# Atmega1280_xmem_512K.net
KiCad netlist of a schematic drawn in EAGLE
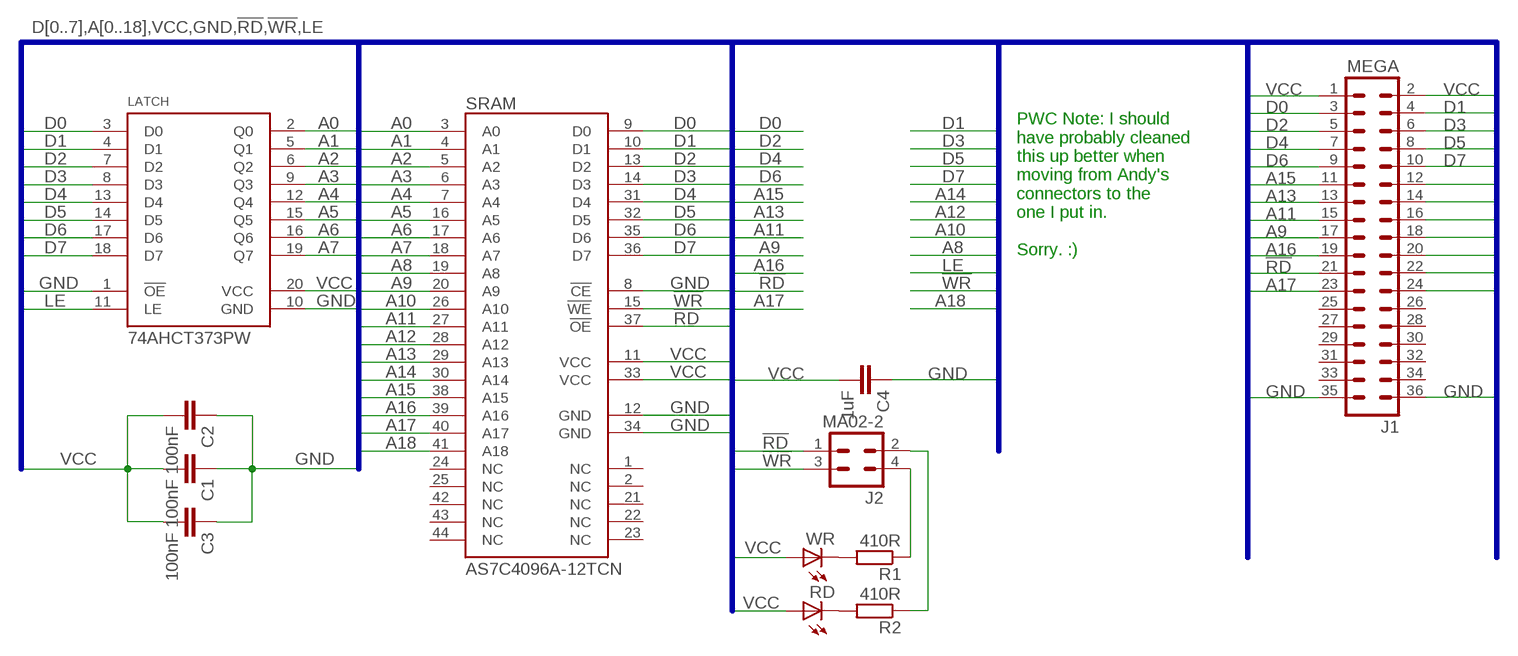
[diagram p0: schematic, sheet 1]

(export (version "E")
  (design (tool "Eeschema 10.0.6"))
  (components
    (comp (ref "C1")
      (value "100nF")
      (footprint "eagle-import:C0603")
      (libsource (lib "eagle-import") (part "C-EUC0603"))
    )
    (comp (ref "C2")
      (value "100nF")
      (footprint "eagle-import:C0603")
      (libsource (lib "eagle-import") (part "C-EUC0603"))
    )
    (comp (ref "C3")
      (value "100nF")
      (footprint "eagle-import:C0603")
      (libsource (lib "eagle-import") (part "C-EUC0603"))
    )
    (comp (ref "C4")
      (value "1uF")
      (footprint "eagle-import:C0603")
      (libsource (lib "eagle-import") (part "C-EUC0603"))
    )
    (comp (ref "J1")
      (value "MEGA")
      (footprint "eagle-import:MA18-2")
      (libsource (lib "eagle-import") (part "MA18-2"))
    )
    (comp (ref "J2")
      (value "MA02-2")
      (footprint "eagle-import:MA02-2")
      (libsource (lib "eagle-import") (part "MA02-2"))
    )
    (comp (ref "LATCH")
      (value "74AHCT373PW")
      (footprint "eagle-import:TSSOP20")
      (libsource (lib "eagle-import") (part "74AHCT373PW"))
    )
    (comp (ref "R1")
      (value "410R")
      (footprint "eagle-import:R0805")
      (libsource (lib "eagle-import") (part "R-EU_R0805"))
    )
    (comp (ref "R2")
      (value "410R")
      (footprint "eagle-import:R0805")
      (libsource (lib "eagle-import") (part "R-EU_R0805"))
    )
    (comp (ref "RD")
      (value "LEDSMT1206")
      (footprint "eagle-import:1206")
      (libsource (lib "eagle-import") (part "LEDSMT1206"))
    )
    (comp (ref "SRAM")
      (value "AS7C4096A-12TCN")
      (footprint "eagle-import:TSOP44-II")
      (libsource (lib "eagle-import") (part "AS7C4096A-12TCN"))
    )
    (comp (ref "WR")
      (value "LEDSMT1206")
      (footprint "eagle-import:1206")
      (libsource (lib "eagle-import") (part "LEDSMT1206"))
    )
  )
  (nets
    (net (code "1") (name "/A0") (class "Default")
      (node (ref "LATCH") (pin "2") (pinfunction "Q0_2") (pintype "bidirectional"))
      (node (ref "SRAM") (pin "3") (pinfunction "A0_3") (pintype "bidirectional"))
    )
    (net (code "2") (name "/A1") (class "Default")
      (node (ref "LATCH") (pin "5") (pinfunction "Q1_5") (pintype "bidirectional"))
      (node (ref "SRAM") (pin "4") (pinfunction "A1_4") (pintype "bidirectional"))
    )
    (net (code "3") (name "/A2") (class "Default")
      (node (ref "LATCH") (pin "6") (pinfunction "Q2_6") (pintype "bidirectional"))
      (node (ref "SRAM") (pin "5") (pinfunction "A2_5") (pintype "bidirectional"))
    )
    (net (code "4") (name "/A3") (class "Default")
      (node (ref "LATCH") (pin "9") (pinfunction "Q3_9") (pintype "bidirectional"))
      (node (ref "SRAM") (pin "6") (pinfunction "A3_6") (pintype "bidirectional"))
    )
    (net (code "5") (name "/A4") (class "Default")
      (node (ref "LATCH") (pin "12") (pinfunction "Q4_12") (pintype "bidirectional"))
      (node (ref "SRAM") (pin "7") (pinfunction "A4_7") (pintype "bidirectional"))
    )
    (net (code "6") (name "/A5") (class "Default")
      (node (ref "LATCH") (pin "15") (pinfunction "Q5_15") (pintype "bidirectional"))
      (node (ref "SRAM") (pin "16") (pinfunction "A5_16") (pintype "bidirectional"))
    )
    (net (code "7") (name "/A6") (class "Default")
      (node (ref "LATCH") (pin "16") (pinfunction "Q6_16") (pintype "bidirectional"))
      (node (ref "SRAM") (pin "17") (pinfunction "A6_17") (pintype "bidirectional"))
    )
    (net (code "8") (name "/A7") (class "Default")
      (node (ref "LATCH") (pin "19") (pinfunction "Q7_19") (pintype "bidirectional"))
      (node (ref "SRAM") (pin "18") (pinfunction "A7_18") (pintype "bidirectional"))
    )
    (net (code "9") (name "/A8") (class "Default")
      (node (ref "J1") (pin "18") (pinfunction "18_18") (pintype "passive"))
      (node (ref "SRAM") (pin "19") (pinfunction "A8_19") (pintype "bidirectional"))
    )
    (net (code "10") (name "/A9") (class "Default")
      (node (ref "J1") (pin "17") (pinfunction "17_17") (pintype "passive"))
      (node (ref "SRAM") (pin "20") (pinfunction "A9_20") (pintype "bidirectional"))
    )
    (net (code "11") (name "/A10") (class "Default")
      (node (ref "J1") (pin "16") (pinfunction "16_16") (pintype "passive"))
      (node (ref "SRAM") (pin "26") (pinfunction "A10_26") (pintype "bidirectional"))
    )
    (net (code "12") (name "/A11") (class "Default")
      (node (ref "J1") (pin "15") (pinfunction "15_15") (pintype "passive"))
      (node (ref "SRAM") (pin "27") (pinfunction "A11_27") (pintype "bidirectional"))
    )
    (net (code "13") (name "/A12") (class "Default")
      (node (ref "J1") (pin "14") (pinfunction "14_14") (pintype "passive"))
      (node (ref "SRAM") (pin "28") (pinfunction "A12_28") (pintype "bidirectional"))
    )
    (net (code "14") (name "/A13") (class "Default")
      (node (ref "J1") (pin "13") (pinfunction "13_13") (pintype "passive"))
      (node (ref "SRAM") (pin "29") (pinfunction "A13_29") (pintype "bidirectional"))
    )
    (net (code "15") (name "/A14") (class "Default")
      (node (ref "J1") (pin "12") (pinfunction "12_12") (pintype "passive"))
      (node (ref "SRAM") (pin "30") (pinfunction "A14_30") (pintype "bidirectional"))
    )
    (net (code "16") (name "/A15") (class "Default")
      (node (ref "J1") (pin "11") (pinfunction "11_11") (pintype "passive"))
      (node (ref "SRAM") (pin "38") (pinfunction "A15_38") (pintype "bidirectional"))
    )
    (net (code "17") (name "/A16") (class "Default")
      (node (ref "J1") (pin "19") (pinfunction "19_19") (pintype "passive"))
      (node (ref "SRAM") (pin "39") (pinfunction "A16_39") (pintype "bidirectional"))
    )
    (net (code "18") (name "/A17") (class "Default")
      (node (ref "J1") (pin "23") (pinfunction "23_23") (pintype "passive"))
      (node (ref "SRAM") (pin "40") (pinfunction "A17_40") (pintype "bidirectional"))
    )
    (net (code "19") (name "/A18") (class "Default")
      (node (ref "J1") (pin "24") (pinfunction "24_24") (pintype "passive"))
      (node (ref "SRAM") (pin "41") (pinfunction "A18_41") (pintype "bidirectional"))
    )
    (net (code "20") (name "/D0") (class "Default")
      (node (ref "J1") (pin "3") (pinfunction "3_3") (pintype "passive"))
      (node (ref "LATCH") (pin "3") (pinfunction "D0_3") (pintype "bidirectional"))
      (node (ref "SRAM") (pin "9") (pinfunction "D0_9") (pintype "bidirectional"))
    )
    (net (code "21") (name "/D1") (class "Default")
      (node (ref "J1") (pin "4") (pinfunction "4_4") (pintype "passive"))
      (node (ref "LATCH") (pin "4") (pinfunction "D1_4") (pintype "bidirectional"))
      (node (ref "SRAM") (pin "10") (pinfunction "D1_10") (pintype "bidirectional"))
    )
    (net (code "22") (name "/D2") (class "Default")
      (node (ref "J1") (pin "5") (pinfunction "5_5") (pintype "passive"))
      (node (ref "LATCH") (pin "7") (pinfunction "D2_7") (pintype "bidirectional"))
      (node (ref "SRAM") (pin "13") (pinfunction "D2_13") (pintype "bidirectional"))
    )
    (net (code "23") (name "/D3") (class "Default")
      (node (ref "J1") (pin "6") (pinfunction "6_6") (pintype "passive"))
      (node (ref "LATCH") (pin "8") (pinfunction "D3_8") (pintype "bidirectional"))
      (node (ref "SRAM") (pin "14") (pinfunction "D3_14") (pintype "bidirectional"))
    )
    (net (code "24") (name "/D4") (class "Default")
      (node (ref "J1") (pin "7") (pinfunction "7_7") (pintype "passive"))
      (node (ref "LATCH") (pin "13") (pinfunction "D4_13") (pintype "bidirectional"))
      (node (ref "SRAM") (pin "31") (pinfunction "D4_31") (pintype "bidirectional"))
    )
    (net (code "25") (name "/D5") (class "Default")
      (node (ref "J1") (pin "8") (pinfunction "8_8") (pintype "passive"))
      (node (ref "LATCH") (pin "14") (pinfunction "D5_14") (pintype "bidirectional"))
      (node (ref "SRAM") (pin "32") (pinfunction "D5_32") (pintype "bidirectional"))
    )
    (net (code "26") (name "/D6") (class "Default")
      (node (ref "J1") (pin "9") (pinfunction "9_9") (pintype "passive"))
      (node (ref "LATCH") (pin "17") (pinfunction "D6_17") (pintype "bidirectional"))
      (node (ref "SRAM") (pin "35") (pinfunction "D6_35") (pintype "bidirectional"))
    )
    (net (code "27") (name "/D7") (class "Default")
      (node (ref "J1") (pin "10") (pinfunction "10_10") (pintype "passive"))
      (node (ref "LATCH") (pin "18") (pinfunction "D7_18") (pintype "bidirectional"))
      (node (ref "SRAM") (pin "36") (pinfunction "D7_36") (pintype "bidirectional"))
    )
    (net (code "28") (name "/GND") (class "Default")
      (node (ref "C1") (pin "1") (pinfunction "1_1") (pintype "passive"))
      (node (ref "C2") (pin "1") (pinfunction "1_1") (pintype "passive"))
      (node (ref "C3") (pin "1") (pinfunction "1_1") (pintype "passive"))
      (node (ref "C4") (pin "1") (pinfunction "1_1") (pintype "passive"))
      (node (ref "J1") (pin "35") (pinfunction "35_35") (pintype "passive"))
      (node (ref "J1") (pin "36") (pinfunction "36_36") (pintype "passive"))
      (node (ref "LATCH") (pin "1") (pinfunction "~{OE}_1") (pintype "bidirectional"))
      (node (ref "LATCH") (pin "10") (pinfunction "GND_10") (pintype "power_in"))
      (node (ref "SRAM") (pin "12") (pinfunction "GND_12") (pintype "power_in"))
      (node (ref "SRAM") (pin "34") (pinfunction "GND_34") (pintype "power_in"))
      (node (ref "SRAM") (pin "8") (pinfunction "~{CE}_8") (pintype "bidirectional"))
    )
    (net (code "29") (name "/LE") (class "Default")
      (node (ref "J1") (pin "20") (pinfunction "20_20") (pintype "passive"))
      (node (ref "LATCH") (pin "11") (pinfunction "LE_11") (pintype "bidirectional"))
    )
    (net (code "30") (name "/VCC") (class "Default")
      (node (ref "C1") (pin "2") (pinfunction "2_2") (pintype "passive"))
      (node (ref "C2") (pin "2") (pinfunction "2_2") (pintype "passive"))
      (node (ref "C3") (pin "2") (pinfunction "2_2") (pintype "passive"))
      (node (ref "C4") (pin "2") (pinfunction "2_2") (pintype "passive"))
      (node (ref "J1") (pin "1") (pinfunction "1_1") (pintype "passive"))
      (node (ref "J1") (pin "2") (pinfunction "2_2") (pintype "passive"))
      (node (ref "LATCH") (pin "20") (pinfunction "VCC_20") (pintype "power_in"))
      (node (ref "RD") (pin "A") (pinfunction "A_A") (pintype "passive"))
      (node (ref "SRAM") (pin "11") (pinfunction "VCC_11") (pintype "power_in"))
      (node (ref "SRAM") (pin "33") (pinfunction "VCC_33") (pintype "power_in"))
      (node (ref "WR") (pin "A") (pinfunction "A_A") (pintype "passive"))
    )
    (net (code "32") (name "/~{RD}") (class "Default")
      (node (ref "J1") (pin "21") (pinfunction "21_21") (pintype "passive"))
      (node (ref "J2") (pin "1") (pinfunction "1_1") (pintype "passive"))
      (node (ref "SRAM") (pin "37") (pinfunction "~{OE}_37") (pintype "bidirectional"))
    )
    (net (code "33") (name "/~{WR}") (class "Default")
      (node (ref "J1") (pin "22") (pinfunction "22_22") (pintype "passive"))
      (node (ref "J2") (pin "3") (pinfunction "3_3") (pintype "passive"))
      (node (ref "SRAM") (pin "15") (pinfunction "~{WE}_15") (pintype "bidirectional"))
    )
    (net (code "34") (name "Net-(J2-Pad2)") (class "Default")
      (node (ref "J2") (pin "2") (pinfunction "2_2") (pintype "passive"))
      (node (ref "R2") (pin "1") (pinfunction "1_1") (pintype "passive"))
    )
    (net (code "35") (name "Net-(J2-Pad4)") (class "Default")
      (node (ref "J2") (pin "4") (pinfunction "4_4") (pintype "passive"))
      (node (ref "R1") (pin "1") (pinfunction "1_1") (pintype "passive"))
    )
    (net (code "36") (name "Net-(R1-Pad2)") (class "Default")
      (node (ref "R1") (pin "2") (pinfunction "2_2") (pintype "passive"))
      (node (ref "WR") (pin "C") (pinfunction "C_C") (pintype "passive"))
    )
    (net (code "37") (name "Net-(R2-Pad2)") (class "Default")
      (node (ref "R2") (pin "2") (pinfunction "2_2") (pintype "passive"))
      (node (ref "RD") (pin "C") (pinfunction "C_C") (pintype "passive"))
    )
    (net (code "38") (name "unconnected-(J1-Pad25)") (class "Default")
      (node (ref "J1") (pin "25") (pinfunction "25_25") (pintype "passive"))
    )
    (net (code "39") (name "unconnected-(J1-Pad26)") (class "Default")
      (node (ref "J1") (pin "26") (pinfunction "26_26") (pintype "passive"))
    )
    (net (code "40") (name "unconnected-(J1-Pad27)") (class "Default")
      (node (ref "J1") (pin "27") (pinfunction "27_27") (pintype "passive"))
    )
    (net (code "41") (name "unconnected-(J1-Pad28)") (class "Default")
      (node (ref "J1") (pin "28") (pinfunction "28_28") (pintype "passive"))
    )
    (net (code "42") (name "unconnected-(J1-Pad29)") (class "Default")
      (node (ref "J1") (pin "29") (pinfunction "29_29") (pintype "passive"))
    )
    (net (code "43") (name "unconnected-(J1-Pad30)") (class "Default")
      (node (ref "J1") (pin "30") (pinfunction "30_30") (pintype "passive"))
    )
    (net (code "44") (name "unconnected-(J1-Pad31)") (class "Default")
      (node (ref "J1") (pin "31") (pinfunction "31_31") (pintype "passive"))
    )
    (net (code "45") (name "unconnected-(J1-Pad32)") (class "Default")
      (node (ref "J1") (pin "32") (pinfunction "32_32") (pintype "passive"))
    )
    (net (code "46") (name "unconnected-(J1-Pad33)") (class "Default")
      (node (ref "J1") (pin "33") (pinfunction "33_33") (pintype "passive"))
    )
    (net (code "47") (name "unconnected-(J1-Pad34)") (class "Default")
      (node (ref "J1") (pin "34") (pinfunction "34_34") (pintype "passive"))
    )
    (net (code "48") (name "unconnected-(SRAM-NC-Pad1)") (class "Default")
      (node (ref "SRAM") (pin "1") (pinfunction "NC_1") (pintype "no_connect"))
    )
    (net (code "49") (name "unconnected-(SRAM-NC-Pad2)") (class "Default")
      (node (ref "SRAM") (pin "2") (pinfunction "NC_2") (pintype "no_connect"))
    )
    (net (code "50") (name "unconnected-(SRAM-NC-Pad21)") (class "Default")
      (node (ref "SRAM") (pin "21") (pinfunction "NC_21") (pintype "no_connect"))
    )
    (net (code "51") (name "unconnected-(SRAM-NC-Pad22)") (class "Default")
      (node (ref "SRAM") (pin "22") (pinfunction "NC_22") (pintype "no_connect"))
    )
    (net (code "52") (name "unconnected-(SRAM-NC-Pad23)") (class "Default")
      (node (ref "SRAM") (pin "23") (pinfunction "NC_23") (pintype "no_connect"))
    )
    (net (code "53") (name "unconnected-(SRAM-NC-Pad24)") (class "Default")
      (node (ref "SRAM") (pin "24") (pinfunction "NC_24") (pintype "no_connect"))
    )
    (net (code "54") (name "unconnected-(SRAM-NC-Pad25)") (class "Default")
      (node (ref "SRAM") (pin "25") (pinfunction "NC_25") (pintype "no_connect"))
    )
    (net (code "55") (name "unconnected-(SRAM-NC-Pad42)") (class "Default")
      (node (ref "SRAM") (pin "42") (pinfunction "NC_42") (pintype "no_connect"))
    )
    (net (code "56") (name "unconnected-(SRAM-NC-Pad43)") (class "Default")
      (node (ref "SRAM") (pin "43") (pinfunction "NC_43") (pintype "no_connect"))
    )
    (net (code "57") (name "unconnected-(SRAM-NC-Pad44)") (class "Default")
      (node (ref "SRAM") (pin "44") (pinfunction "NC_44") (pintype "no_connect"))
    )
  )
)
